# WIFI.net
KiCad netlist of a schematic drawn in Altium Designer
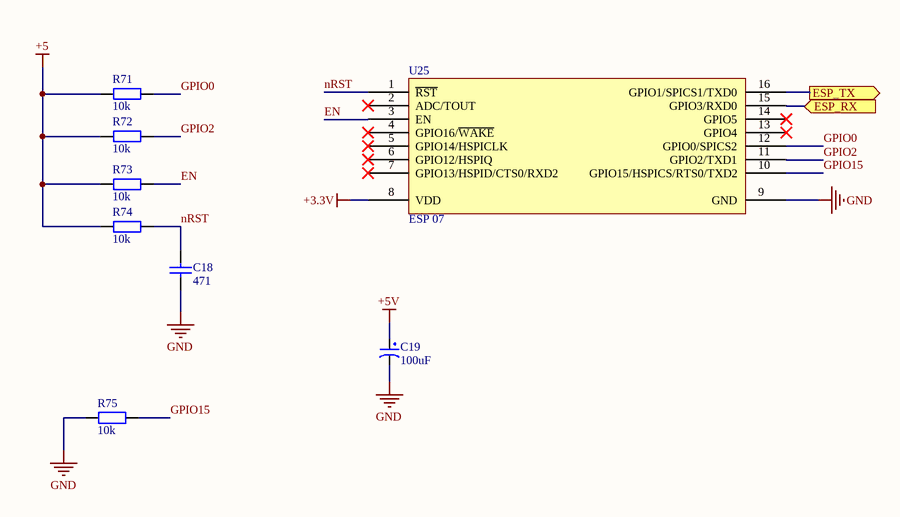
[diagram p0: WIFI.SchDoc]

(export (version "E")
  (design (tool "Eeschema 10.0.6"))
  (components
    (comp (ref "C18")
      (value "471")
      (footprint "tu 0805")
      (description "Dán")
      (libsource (lib "Altium_Lib_by_KhueNguyenCreator") (part "Tu 0805 471 50V 10%"))
    )
    (comp (ref "C19")
      (value "100uF")
      (footprint "tu hoa 5mm")
      (description "Cắm")
      (libsource (lib "Altium_Lib_by_KhueNguyenCreator") (part "Tu Hoa 100uF 16V 5x7"))
    )
    (comp (ref "R71")
      (value "10k")
      (footprint "tro smd 0805")
      (description "Dán")
      (libsource (lib "Altium_Lib_by_KhueNguyenCreator") (part "Tro 0805 1% 10k"))
    )
    (comp (ref "R72")
      (value "10k")
      (footprint "tro smd 0805")
      (description "Dán")
      (libsource (lib "Altium_Lib_by_KhueNguyenCreator") (part "Tro 0805 1% 10k"))
    )
    (comp (ref "R73")
      (value "10k")
      (footprint "tro smd 0805")
      (description "Dán")
      (libsource (lib "Altium_Lib_by_KhueNguyenCreator") (part "Tro 0805 1% 10k"))
    )
    (comp (ref "R74")
      (value "10k")
      (footprint "tro smd 0805")
      (description "Dán")
      (libsource (lib "Altium_Lib_by_KhueNguyenCreator") (part "Tro 0805 1% 10k"))
    )
    (comp (ref "R75")
      (value "10k")
      (footprint "tro smd 0805")
      (description "Dán")
      (libsource (lib "Altium_Lib_by_KhueNguyenCreator") (part "Tro 0805 1% 10k"))
    )
    (comp (ref "U25")
      (value "ESP 07")
      (footprint "ESP8266 07")
      (description "ESP8266 07 16 Pin")
      (libsource (lib "Altium_Lib_by_KhueNguyenCreator") (part "ESP8266 07"))
    )
  )
  (nets
    (net (code "1") (name "+3.3V") (class "Default")
      (node (ref "U25") (pin "8") (pinfunction "VDD_8") (pintype "passive"))
    )
    (net (code "2") (name "+5") (class "Default")
      (node (ref "R71") (pin "2") (pinfunction "2_2") (pintype "passive"))
      (node (ref "R72") (pin "2") (pinfunction "2_2") (pintype "passive"))
      (node (ref "R73") (pin "2") (pinfunction "2_2") (pintype "passive"))
      (node (ref "R74") (pin "2") (pinfunction "2_2") (pintype "passive"))
    )
    (net (code "3") (name "+5V") (class "Default")
      (node (ref "C19") (pin "1") (pinfunction "1_1") (pintype "passive"))
    )
    (net (code "4") (name "/EN") (class "Default")
      (node (ref "R73") (pin "1") (pinfunction "1_1") (pintype "passive"))
      (node (ref "U25") (pin "3") (pinfunction "EN_3") (pintype "passive"))
    )
    (net (code "5") (name "/ESP_RX") (class "Default")
      (node (ref "U25") (pin "15") (pinfunction "GPIO3/RXD0_15") (pintype "passive"))
    )
    (net (code "6") (name "/ESP_TX") (class "Default")
      (node (ref "U25") (pin "16") (pinfunction "GPIO1/SPICS1/TXD0_16") (pintype "passive"))
    )
    (net (code "7") (name "/GPIO0") (class "Default")
      (node (ref "R71") (pin "1") (pinfunction "1_1") (pintype "passive"))
      (node (ref "U25") (pin "12") (pinfunction "GPIO0/SPICS2_12") (pintype "passive"))
    )
    (net (code "8") (name "/GPIO2") (class "Default")
      (node (ref "R72") (pin "1") (pinfunction "1_1") (pintype "passive"))
      (node (ref "U25") (pin "11") (pinfunction "GPIO2/TXD1_11") (pintype "passive"))
    )
    (net (code "9") (name "/GPIO15") (class "Default")
      (node (ref "R75") (pin "1") (pinfunction "1_1") (pintype "passive"))
      (node (ref "U25") (pin "10") (pinfunction "GPIO15/HSPICS/RTS0/TXD2_10") (pintype "passive"))
    )
    (net (code "10") (name "/nRST") (class "Default")
      (node (ref "C18") (pin "1") (pinfunction "1_1") (pintype "passive"))
      (node (ref "R74") (pin "1") (pinfunction "1_1") (pintype "passive"))
      (node (ref "U25") (pin "1") (pinfunction "~{RST}_1") (pintype "passive"))
    )
    (net (code "11") (name "GND") (class "Default")
      (node (ref "C18") (pin "2") (pinfunction "2_2") (pintype "passive"))
      (node (ref "C19") (pin "2") (pinfunction "2_2") (pintype "passive"))
      (node (ref "R75") (pin "2") (pinfunction "2_2") (pintype "passive"))
      (node (ref "U25") (pin "9") (pinfunction "GND_9") (pintype "passive"))
    )
    (net (code "12") (name "unconnected-(U25-ADC{slash}TOUT-Pad2)") (class "Default")
      (node (ref "U25") (pin "2") (pinfunction "ADC/TOUT_2") (pintype "passive+no_connect"))
    )
    (net (code "13") (name "unconnected-(U25-GPIO4-Pad13)") (class "Default")
      (node (ref "U25") (pin "13") (pinfunction "GPIO4_13") (pintype "passive+no_connect"))
    )
    (net (code "14") (name "unconnected-(U25-GPIO5-Pad14)") (class "Default")
      (node (ref "U25") (pin "14") (pinfunction "GPIO5_14") (pintype "passive+no_connect"))
    )
    (net (code "15") (name "unconnected-(U25-GPIO12{slash}HSPIQ-Pad6)") (class "Default")
      (node (ref "U25") (pin "6") (pinfunction "GPIO12/HSPIQ_6") (pintype "passive+no_connect"))
    )
    (net (code "16") (name "unconnected-(U25-GPIO13{slash}HSPID{slash}CTS0{slash}RXD2-Pad7)") (class "Default")
      (node (ref "U25") (pin "7") (pinfunction "GPIO13/HSPID/CTS0/RXD2_7") (pintype "passive+no_connect"))
    )
    (net (code "17") (name "unconnected-(U25-GPIO14{slash}HSPICLK-Pad5)") (class "Default")
      (node (ref "U25") (pin "5") (pinfunction "GPIO14/HSPICLK_5") (pintype "passive+no_connect"))
    )
    (net (code "18") (name "unconnected-(U25-GPIO16{slash}~{WAKE}-Pad4)") (class "Default")
      (node (ref "U25") (pin "4") (pinfunction "GPIO16/~{WAKE}_4") (pintype "passive+no_connect"))
    )
  )
)
